# Fri3D_IRA_ESP32.net
KiCad netlist of a schematic drawn in Altium Designer
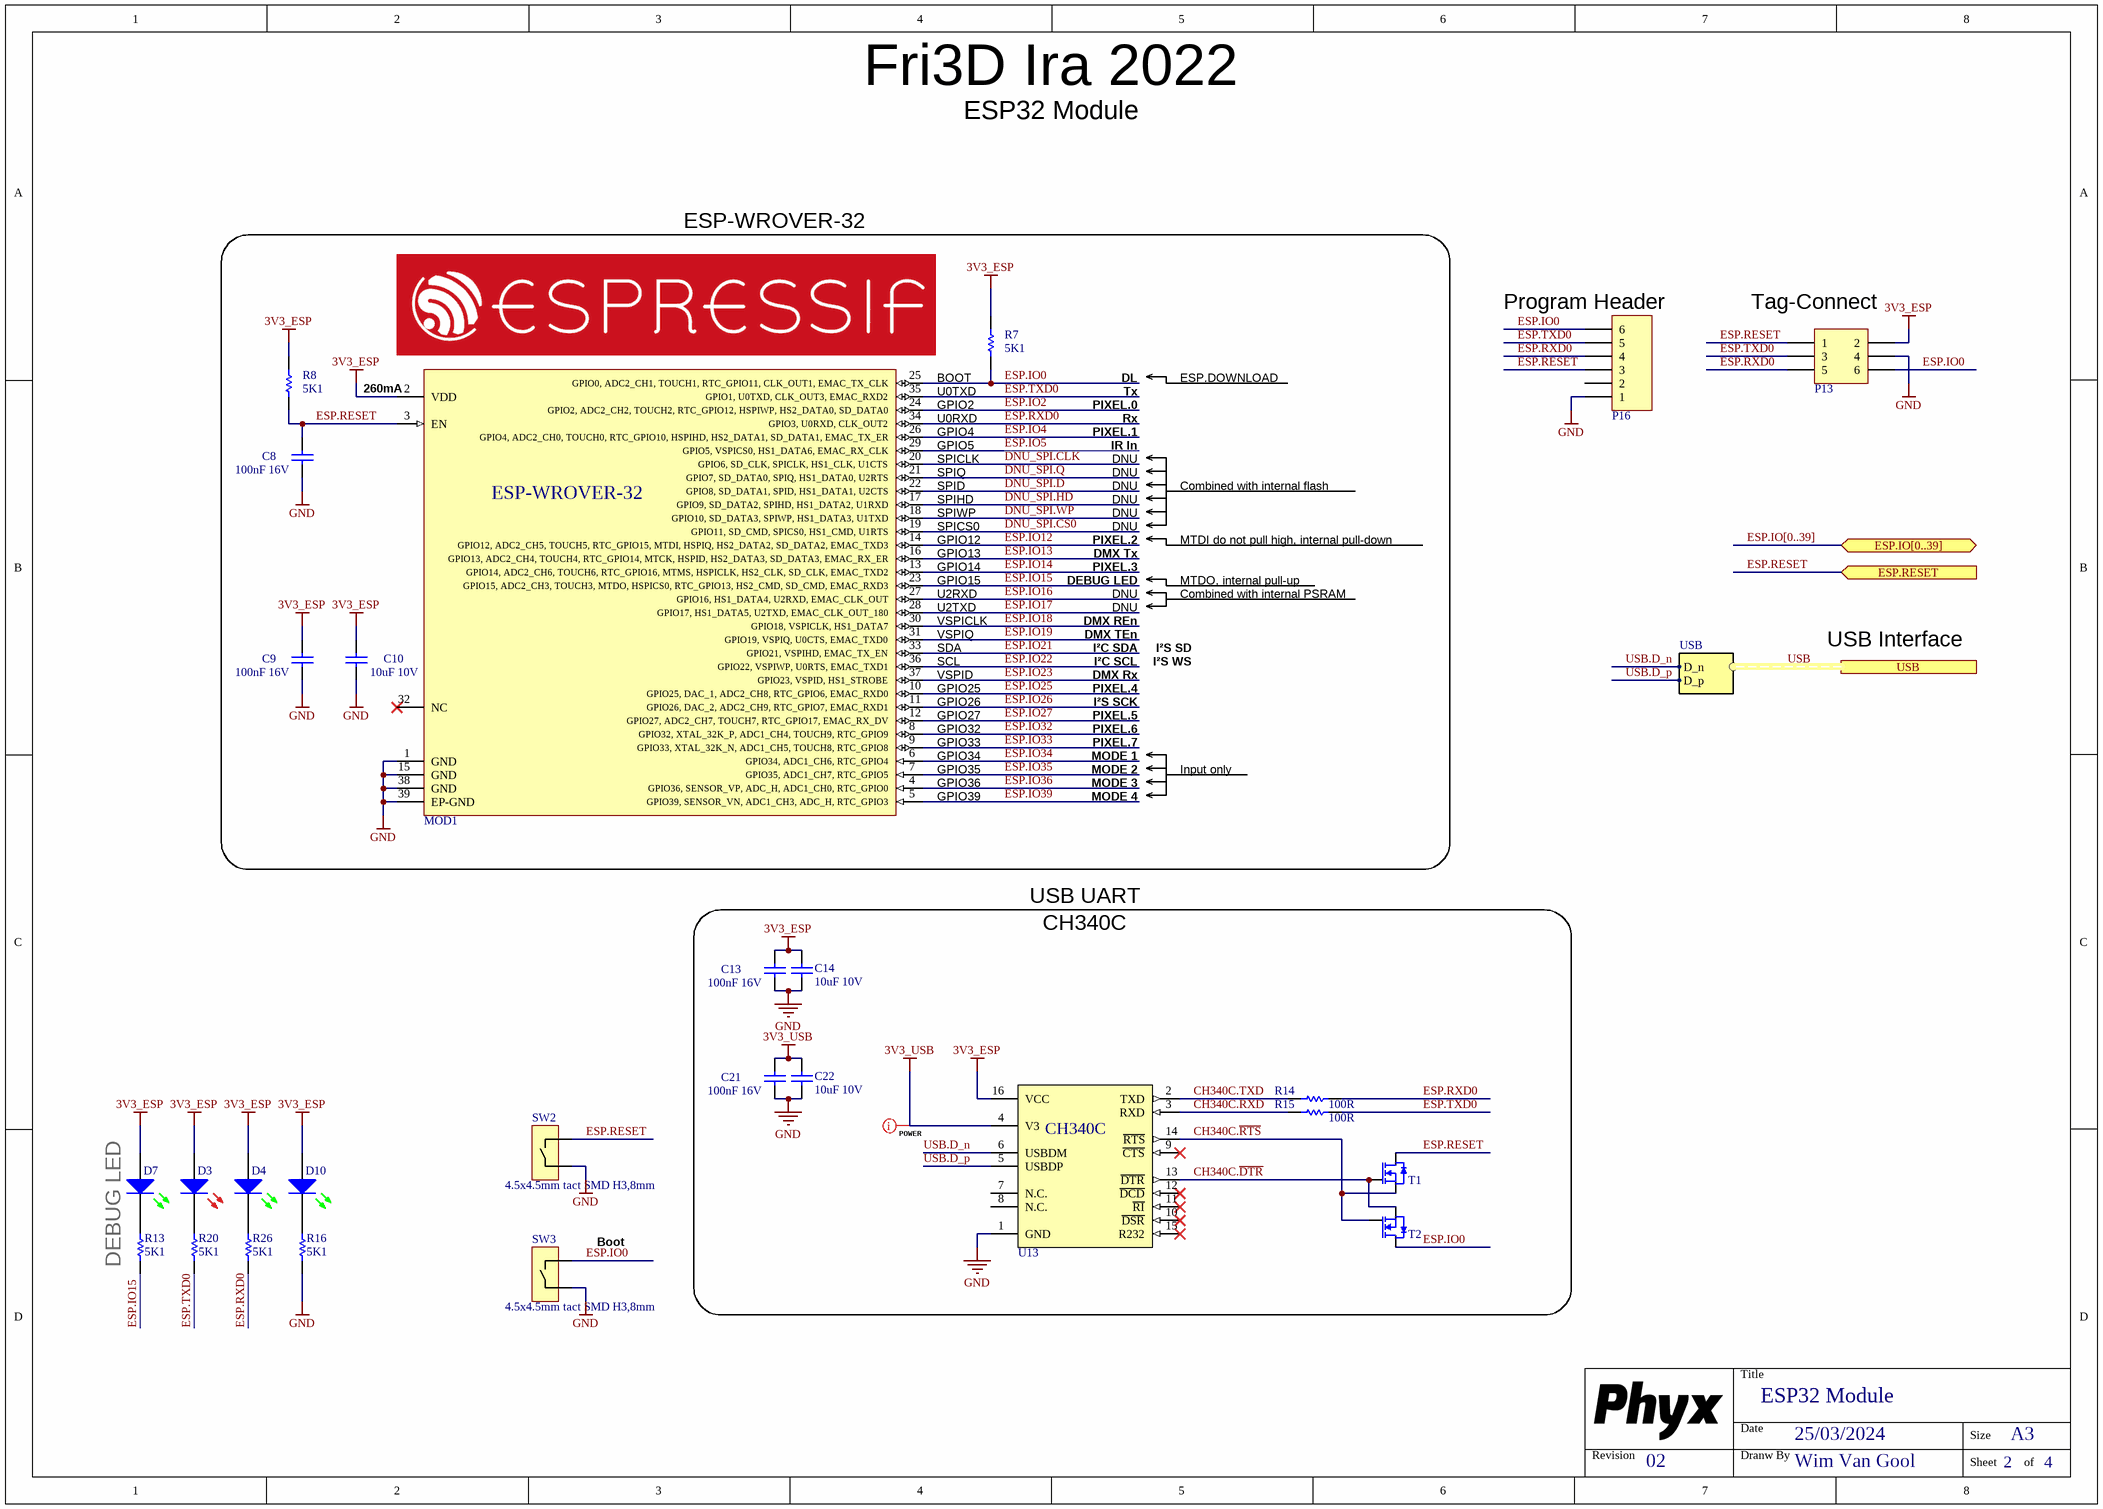
[diagram p0: Fri3D_IRA_ESP32.SchDoc]

(export (version "E")
  (design (tool "Eeschema 10.0.6"))
  (components
    (comp (ref "C8")
      (value "100nF 16V")
      (footprint "C0603_N")
      (description "Capacitor Ceramic")
      (libsource (lib "Phyx_Components") (part "CAP_CERAMIC"))
    )
    (comp (ref "C9")
      (value "100nF 16V")
      (footprint "C0603_N")
      (description "Capacitor Ceramic")
      (libsource (lib "Phyx_Components") (part "CAP_CERAMIC"))
    )
    (comp (ref "C10")
      (value "10uF 10V")
      (footprint "C0805_N")
      (description "Capacitor Ceramic")
      (libsource (lib "Phyx_Components") (part "CAP_CERAMIC"))
    )
    (comp (ref "C13")
      (value "100nF 16V")
      (footprint "C0603_N")
      (description "Capacitor Ceramic")
      (libsource (lib "Phyx_Components") (part "CAP_CERAMIC"))
    )
    (comp (ref "C14")
      (value "10uF 10V")
      (footprint "C0805_N")
      (description "Capacitor Ceramic")
      (libsource (lib "Phyx_Components") (part "CAP_CERAMIC"))
    )
    (comp (ref "C21")
      (value "100nF 16V")
      (footprint "C0603_N")
      (description "Capacitor Ceramic")
      (libsource (lib "Phyx_Components") (part "CAP_CERAMIC"))
    )
    (comp (ref "C22")
      (value "10uF 10V")
      (footprint "C0805_N")
      (description "Capacitor Ceramic")
      (libsource (lib "Phyx_Components") (part "CAP_CERAMIC"))
    )
    (comp (ref "D3")
      (value "Default 0805 Red LED")
      (footprint "LED_0805_RD")
      (description "=Description")
      (libsource (lib "Phyx_Components") (part "LED_RED"))
    )
    (comp (ref "D4")
      (value "Default 0805 Green LED")
      (footprint "LED_0805_GR")
      (description "=Description")
      (libsource (lib "Phyx_Components") (part "LED_GREEN"))
    )
    (comp (ref "D7")
      (value "Default 0805 Green LED")
      (footprint "LED_0805_GR")
      (description "=Description")
      (libsource (lib "Phyx_Components") (part "LED_GREEN"))
    )
    (comp (ref "D10")
      (value "Default 0805 Green LED")
      (footprint "LED_0805_GR")
      (description "=Description")
      (libsource (lib "Phyx_Components") (part "LED_GREEN"))
    )
    (comp (ref "MOD1")
      (value "ESP-32 based ESP-WROVER-32")
      (footprint "ESP-WROVER-32")
      (description "WiFi # MOD ESP-WROVER-32")
      (libsource (lib "Phyx_Components") (part "ESP-WROVER-32"))
    )
    (comp (ref "P13")
      (value "6 pin tagconnect TC2030")
      (footprint "TC2030")
      (libsource (lib "Phyx_Components") (part "Header 3X2"))
    )
    (comp (ref "P16")
      (value "Header 6")
      (footprint "HDR1X6")
      (libsource (lib "Phyx_Components") (part "Header 6"))
    )
    (comp (ref "R7")
      (value "5K1")
      (footprint "R0603_N")
      (libsource (lib "Phyx_Components") (part "RESISTOR"))
    )
    (comp (ref "R8")
      (value "5K1")
      (footprint "R0603_N")
      (libsource (lib "Phyx_Components") (part "RESISTOR"))
    )
    (comp (ref "R13")
      (value "5K1")
      (footprint "R0603_N")
      (libsource (lib "Phyx_Components") (part "RESISTOR"))
    )
    (comp (ref "R14")
      (value "100R")
      (footprint "R0603_N")
      (libsource (lib "Phyx_Components") (part "RESISTOR"))
    )
    (comp (ref "R15")
      (value "100R")
      (footprint "R0603_N")
      (libsource (lib "Phyx_Components") (part "RESISTOR"))
    )
    (comp (ref "R16")
      (value "5K1")
      (footprint "R0603_N")
      (libsource (lib "Phyx_Components") (part "RESISTOR"))
    )
    (comp (ref "R20")
      (value "5K1")
      (footprint "R0603_N")
      (description "RES # 5K1 0603")
      (libsource (lib "Phyx_Components") (part "RESISTOR"))
    )
    (comp (ref "R26")
      (value "5K1")
      (footprint "R0603_N")
      (description "RES # 5K1 0603")
      (libsource (lib "Phyx_Components") (part "RESISTOR"))
    )
    (comp (ref "SW2")
      (value "4.5x4.5mm tact SMD H3,8mm")
      (footprint "WE_430181038816")
      (libsource (lib "Phyx_Components") (part "SW_TACT"))
    )
    (comp (ref "SW3")
      (value "4.5x4.5mm tact SMD H3,8mm")
      (footprint "WE_430181038816")
      (libsource (lib "Phyx_Components") (part "SW_TACT"))
    )
    (comp (ref "T1")
      (value "0.2A N-Ch MOSFET Vgs 3.2")
      (footprint "SOT23-3")
      (libsource (lib "Phyx_Components") (part "N_MOSFET_GSD"))
    )
    (comp (ref "T2")
      (value "0.2A N-Ch MOSFET Vgs 3.2")
      (footprint "SOT23-3")
      (libsource (lib "Phyx_Components") (part "N_MOSFET_GSD"))
    )
    (comp (ref "U13")
      (value "USB to full UART with internal crystal")
      (footprint "SOIC_N_16")
      (description "=Description")
      (libsource (lib "Phyx_Components") (part "CH340C"))
    )
  )
  (nets
    (net (code "18") (name "/CH340C.RXD") (class "Default")
      (node (ref "R15") (pin "1") (pinfunction "1_1") (pintype "passive"))
      (node (ref "U13") (pin "3") (pinfunction "RXD_3") (pintype "input"))
    )
    (net (code "19") (name "/CH340C.TXD") (class "Default")
      (node (ref "R14") (pin "1") (pinfunction "1_1") (pintype "passive"))
      (node (ref "U13") (pin "2") (pinfunction "TXD_2") (pintype "output"))
    )
    (net (code "20") (name "/CH340C.~{DTR}") (class "Default")
      (node (ref "T1") (pin "1") (pinfunction "G_1") (pintype "passive"))
      (node (ref "T2") (pin "2") (pinfunction "S_2") (pintype "passive"))
      (node (ref "U13") (pin "13") (pinfunction "~{DTR}_13") (pintype "output"))
    )
    (net (code "21") (name "/CH340C.~{RTS}") (class "Default")
      (node (ref "T1") (pin "2") (pinfunction "S_2") (pintype "passive"))
      (node (ref "T2") (pin "1") (pinfunction "G_1") (pintype "passive"))
      (node (ref "U13") (pin "14") (pinfunction "~{RTS}_14") (pintype "output"))
    )
    (net (code "22") (name "/DNU_SPI.CLK") (class "Default")
      (node (ref "MOD1") (pin "20") (pinfunction "GPIO6,_SD_CLK,_SPICLK,_HS1_CLK,_U1CTS_20") (pintype "bidirectional"))
    )
    (net (code "23") (name "/DNU_SPI.CS0") (class "Default")
      (node (ref "MOD1") (pin "19") (pinfunction "GPIO11,_SD_CMD,_SPICS0,_HS1_CMD,_U1RTS_19") (pintype "bidirectional"))
    )
    (net (code "24") (name "/DNU_SPI.D") (class "Default")
      (node (ref "MOD1") (pin "22") (pinfunction "GPIO8,_SD_DATA1,_SPID,_HS1_DATA1,_U2CTS_22") (pintype "bidirectional"))
    )
    (net (code "25") (name "/DNU_SPI.HD") (class "Default")
      (node (ref "MOD1") (pin "17") (pinfunction "GPIO9,_SD_DATA2,_SPIHD,_HS1_DATA2,_U1RXD_17") (pintype "bidirectional"))
    )
    (net (code "26") (name "/DNU_SPI.Q") (class "Default")
      (node (ref "MOD1") (pin "21") (pinfunction "GPIO7,_SD_DATA0,_SPIQ,_HS1_DATA0,_U2RTS_21") (pintype "bidirectional"))
    )
    (net (code "27") (name "/DNU_SPI.WP") (class "Default")
      (node (ref "MOD1") (pin "18") (pinfunction "GPIO10,_SD_DATA3,_SPIWP,_HS1_DATA3,_U1TXD_18") (pintype "bidirectional"))
    )
    (net (code "28") (name "/ESP.IO0") (class "Default")
      (node (ref "MOD1") (pin "25") (pinfunction "GPIO0,_ADC2_CH1,_TOUCH1,_RTC_GPIO11,_CLK_OUT1,_EMAC_TX_CLK_25") (pintype "bidirectional"))
      (node (ref "P13") (pin "6") (pinfunction "6_6") (pintype "passive"))
      (node (ref "P16") (pin "6") (pinfunction "6_6") (pintype "passive"))
      (node (ref "R7") (pin "2") (pinfunction "2_2") (pintype "passive"))
      (node (ref "SW3") (pin "1") (pinfunction "1_1") (pintype "passive"))
      (node (ref "T2") (pin "3") (pinfunction "D_3") (pintype "passive"))
    )
    (net (code "29") (name "/ESP.IO2") (class "Default")
      (node (ref "MOD1") (pin "24") (pinfunction "GPIO2,_ADC2_CH2,_TOUCH2,_RTC_GPIO12,_HSPIWP,_HS2_DATA0,_SD_DATA0_24") (pintype "bidirectional"))
    )
    (net (code "30") (name "/ESP.IO4") (class "Default")
      (node (ref "MOD1") (pin "26") (pinfunction "GPIO4,_ADC2_CH0,_TOUCH0,_RTC_GPIO10,_HSPIHD,_HS2_DATA1,_SD_DATA1,_EMAC_TX_ER_26") (pintype "bidirectional"))
    )
    (net (code "31") (name "/ESP.IO5") (class "Default")
      (node (ref "MOD1") (pin "29") (pinfunction "GPIO5,_VSPICS0,_HS1_DATA6,_EMAC_RX_CLK_29") (pintype "bidirectional"))
    )
    (net (code "32") (name "/ESP.IO12") (class "Default")
      (node (ref "MOD1") (pin "14") (pinfunction "GPIO12,_ADC2_CH5,_TOUCH5,_RTC_GPIO15,_MTDI,_HSPIQ,_HS2_DATA2,_SD_DATA2,_EMAC_TXD3_14") (pintype "bidirectional"))
    )
    (net (code "33") (name "/ESP.IO13") (class "Default")
      (node (ref "MOD1") (pin "16") (pinfunction "GPIO13,_ADC2_CH4,_TOUCH4,_RTC_GPIO14,_MTCK,_HSPID,_HS2_DATA3,_SD_DATA3,_EMAC_RX_ER_16") (pintype "bidirectional"))
    )
    (net (code "34") (name "/ESP.IO14") (class "Default")
      (node (ref "MOD1") (pin "13") (pinfunction "GPIO14,_ADC2_CH6,_TOUCH6,_RTC_GPIO16,_MTMS,_HSPICLK,_HS2_CLK,_SD_CLK,_EMAC_TXD2_13") (pintype "bidirectional"))
    )
    (net (code "35") (name "/ESP.IO15") (class "Default")
      (node (ref "MOD1") (pin "23") (pinfunction "GPIO15,_ADC2_CH3,_TOUCH3,_MTDO,_HSPICS0,_RTC_GPIO13,_HS2_CMD,_SD_CMD,_EMAC_RXD3_23") (pintype "bidirectional"))
      (node (ref "R13") (pin "2") (pinfunction "2_2") (pintype "passive"))
    )
    (net (code "36") (name "/ESP.IO16") (class "Default")
      (node (ref "MOD1") (pin "27") (pinfunction "GPIO16,_HS1_DATA4,_U2RXD,_EMAC_CLK_OUT_27") (pintype "bidirectional"))
    )
    (net (code "37") (name "/ESP.IO17") (class "Default")
      (node (ref "MOD1") (pin "28") (pinfunction "GPIO17,_HS1_DATA5,_U2TXD,_EMAC_CLK_OUT_180_28") (pintype "bidirectional"))
    )
    (net (code "38") (name "/ESP.IO18") (class "Default")
      (node (ref "MOD1") (pin "30") (pinfunction "GPIO18,_VSPICLK,_HS1_DATA7_30") (pintype "bidirectional"))
    )
    (net (code "39") (name "/ESP.IO19") (class "Default")
      (node (ref "MOD1") (pin "31") (pinfunction "GPIO19,_VSPIQ,_U0CTS,_EMAC_TXD0_31") (pintype "bidirectional"))
    )
    (net (code "40") (name "/ESP.IO21") (class "Default")
      (node (ref "MOD1") (pin "33") (pinfunction "GPIO21,_VSPIHD,_EMAC_TX_EN_33") (pintype "bidirectional"))
    )
    (net (code "41") (name "/ESP.IO22") (class "Default")
      (node (ref "MOD1") (pin "36") (pinfunction "GPIO22,_VSPIWP,_U0RTS,_EMAC_TXD1_36") (pintype "bidirectional"))
    )
    (net (code "42") (name "/ESP.IO23") (class "Default")
      (node (ref "MOD1") (pin "37") (pinfunction "GPIO23,_VSPID,_HS1_STROBE_37") (pintype "bidirectional"))
    )
    (net (code "43") (name "/ESP.IO25") (class "Default")
      (node (ref "MOD1") (pin "10") (pinfunction "GPIO25,_DAC_1,_ADC2_CH8,_RTC_GPIO6,_EMAC_RXD0_10") (pintype "bidirectional"))
    )
    (net (code "44") (name "/ESP.IO26") (class "Default")
      (node (ref "MOD1") (pin "11") (pinfunction "GPIO26,_DAC_2,_ADC2_CH9,_RTC_GPIO7,_EMAC_RXD1_11") (pintype "bidirectional"))
    )
    (net (code "45") (name "/ESP.IO27") (class "Default")
      (node (ref "MOD1") (pin "12") (pinfunction "GPIO27,_ADC2_CH7,_TOUCH7,_RTC_GPIO17,_EMAC_RX_DV_12") (pintype "bidirectional"))
    )
    (net (code "46") (name "/ESP.IO32") (class "Default")
      (node (ref "MOD1") (pin "8") (pinfunction "GPIO32,_XTAL_32K_P,_ADC1_CH4,_TOUCH9,_RTC_GPIO9_8") (pintype "bidirectional"))
    )
    (net (code "47") (name "/ESP.IO33") (class "Default")
      (node (ref "MOD1") (pin "9") (pinfunction "GPIO33,_XTAL_32K_N,_ADC1_CH5,_TOUCH8,_RTC_GPIO8_9") (pintype "bidirectional"))
    )
    (net (code "48") (name "/ESP.IO34") (class "Default")
      (node (ref "MOD1") (pin "6") (pinfunction "GPIO34,_ADC1_CH6,_RTC_GPIO4_6") (pintype "input"))
    )
    (net (code "49") (name "/ESP.IO35") (class "Default")
      (node (ref "MOD1") (pin "7") (pinfunction "GPIO35,_ADC1_CH7,_RTC_GPIO5_7") (pintype "input"))
    )
    (net (code "50") (name "/ESP.IO36") (class "Default")
      (node (ref "MOD1") (pin "4") (pinfunction "GPIO36,_SENSOR_VP,_ADC_H,_ADC1_CH0,_RTC_GPIO0_4") (pintype "input"))
    )
    (net (code "51") (name "/ESP.IO39") (class "Default")
      (node (ref "MOD1") (pin "5") (pinfunction "GPIO39,_SENSOR_VN,_ADC1_CH3,_ADC_H,_RTC_GPIO3_5") (pintype "input"))
    )
    (net (code "53") (name "/ESP.RESET") (class "Default")
      (node (ref "C8") (pin "1") (pinfunction "1_1") (pintype "passive"))
      (node (ref "MOD1") (pin "3") (pinfunction "EN_3") (pintype "input"))
      (node (ref "P13") (pin "1") (pinfunction "1_1") (pintype "passive"))
      (node (ref "P16") (pin "3") (pinfunction "3_3") (pintype "passive"))
      (node (ref "R8") (pin "2") (pinfunction "2_2") (pintype "passive"))
      (node (ref "SW2") (pin "1") (pinfunction "1_1") (pintype "passive"))
      (node (ref "T1") (pin "3") (pinfunction "D_3") (pintype "passive"))
    )
    (net (code "54") (name "/ESP.RXD0") (class "Default")
      (node (ref "MOD1") (pin "34") (pinfunction "GPIO3,_U0RXD,_CLK_OUT2_34") (pintype "bidirectional"))
      (node (ref "P13") (pin "5") (pinfunction "5_5") (pintype "passive"))
      (node (ref "P16") (pin "4") (pinfunction "4_4") (pintype "passive"))
      (node (ref "R14") (pin "2") (pinfunction "2_2") (pintype "passive"))
      (node (ref "R26") (pin "2") (pinfunction "2_2") (pintype "passive"))
    )
    (net (code "55") (name "/ESP.TXD0") (class "Default")
      (node (ref "MOD1") (pin "35") (pinfunction "GPIO1,_U0TXD,_CLK_OUT3,_EMAC_RXD2_35") (pintype "bidirectional"))
      (node (ref "P13") (pin "3") (pinfunction "3_3") (pintype "passive"))
      (node (ref "P16") (pin "5") (pinfunction "5_5") (pintype "passive"))
      (node (ref "R15") (pin "2") (pinfunction "2_2") (pintype "passive"))
      (node (ref "R20") (pin "2") (pinfunction "2_2") (pintype "passive"))
    )
    (net (code "56") (name "/USB.D_n") (class "Default")
      (node (ref "U13") (pin "6") (pinfunction "USBDM_6") (pintype "passive"))
    )
    (net (code "57") (name "/USB.D_p") (class "Default")
      (node (ref "U13") (pin "5") (pinfunction "USBDP_5") (pintype "passive"))
    )
    (net (code "59") (name "3V3_ESP") (class "Default")
      (node (ref "C10") (pin "1") (pinfunction "1_1") (pintype "passive"))
      (node (ref "C13") (pin "1") (pinfunction "1_1") (pintype "passive"))
      (node (ref "C14") (pin "2") (pinfunction "2_2") (pintype "passive"))
      (node (ref "C9") (pin "1") (pinfunction "1_1") (pintype "passive"))
      (node (ref "D10") (pin "1") (pinfunction "A_1") (pintype "passive"))
      (node (ref "D3") (pin "1") (pinfunction "A_1") (pintype "passive"))
      (node (ref "D4") (pin "1") (pinfunction "A_1") (pintype "passive"))
      (node (ref "D7") (pin "1") (pinfunction "A_1") (pintype "passive"))
      (node (ref "MOD1") (pin "2") (pinfunction "VDD_2") (pintype "power_in"))
      (node (ref "P13") (pin "2") (pinfunction "2_2") (pintype "passive"))
      (node (ref "R7") (pin "1") (pinfunction "1_1") (pintype "passive"))
      (node (ref "R8") (pin "1") (pinfunction "1_1") (pintype "passive"))
      (node (ref "U13") (pin "16") (pinfunction "VCC_16") (pintype "power_in"))
    )
    (net (code "60") (name "3V3_USB") (class "Default")
      (node (ref "C21") (pin "1") (pinfunction "1_1") (pintype "passive"))
      (node (ref "C22") (pin "2") (pinfunction "2_2") (pintype "passive"))
      (node (ref "U13") (pin "4") (pinfunction "V3_4") (pintype "power_in"))
    )
    (net (code "61") (name "GND") (class "Default")
      (node (ref "C10") (pin "2") (pinfunction "2_2") (pintype "passive"))
      (node (ref "C13") (pin "2") (pinfunction "2_2") (pintype "passive"))
      (node (ref "C14") (pin "1") (pinfunction "1_1") (pintype "passive"))
      (node (ref "C21") (pin "2") (pinfunction "2_2") (pintype "passive"))
      (node (ref "C22") (pin "1") (pinfunction "1_1") (pintype "passive"))
      (node (ref "C8") (pin "2") (pinfunction "2_2") (pintype "passive"))
      (node (ref "C9") (pin "2") (pinfunction "2_2") (pintype "passive"))
      (node (ref "MOD1") (pin "1") (pinfunction "GND_1") (pintype "power_in"))
      (node (ref "MOD1") (pin "15") (pinfunction "GND_15") (pintype "power_in"))
      (node (ref "MOD1") (pin "38") (pinfunction "GND_38") (pintype "power_in"))
      (node (ref "MOD1") (pin "39") (pinfunction "EP-GND_39") (pintype "power_in"))
      (node (ref "P13") (pin "4") (pinfunction "4_4") (pintype "passive"))
      (node (ref "P16") (pin "1") (pinfunction "1_1") (pintype "passive"))
      (node (ref "R16") (pin "2") (pinfunction "2_2") (pintype "passive"))
      (node (ref "SW2") (pin "2") (pinfunction "2_2") (pintype "passive"))
      (node (ref "SW3") (pin "2") (pinfunction "2_2") (pintype "passive"))
      (node (ref "U13") (pin "1") (pinfunction "GND_1") (pintype "power_in"))
    )
    (net (code "62") (name "Net-(D3-K)") (class "Default")
      (node (ref "D3") (pin "2") (pinfunction "K_2") (pintype "passive"))
      (node (ref "R20") (pin "1") (pinfunction "1_1") (pintype "passive"))
    )
    (net (code "63") (name "Net-(D4-K)") (class "Default")
      (node (ref "D4") (pin "2") (pinfunction "K_2") (pintype "passive"))
      (node (ref "R26") (pin "1") (pinfunction "1_1") (pintype "passive"))
    )
    (net (code "64") (name "Net-(D7-K)") (class "Default")
      (node (ref "D7") (pin "2") (pinfunction "K_2") (pintype "passive"))
      (node (ref "R13") (pin "1") (pinfunction "1_1") (pintype "passive"))
    )
    (net (code "65") (name "Net-(D10-K)") (class "Default")
      (node (ref "D10") (pin "2") (pinfunction "K_2") (pintype "passive"))
      (node (ref "R16") (pin "1") (pinfunction "1_1") (pintype "passive"))
    )
    (net (code "66") (name "unconnected-(MOD1-NC-Pad32)") (class "Default")
      (node (ref "MOD1") (pin "32") (pinfunction "NC_32") (pintype "passive+no_connect"))
    )
    (net (code "67") (name "unconnected-(P16-Pad2)") (class "Default")
      (node (ref "P16") (pin "2") (pinfunction "2_2") (pintype "passive"))
    )
    (net (code "68") (name "unconnected-(U13-N.C.-Pad7)") (class "Default")
      (node (ref "U13") (pin "7") (pinfunction "N.C._7") (pintype "passive"))
    )
    (net (code "69") (name "unconnected-(U13-N.C.-Pad8)") (class "Default")
      (node (ref "U13") (pin "8") (pinfunction "N.C._8") (pintype "passive"))
    )
    (net (code "70") (name "unconnected-(U13-R232-Pad15)") (class "Default")
      (node (ref "U13") (pin "15") (pinfunction "R232_15") (pintype "input+no_connect"))
    )
    (net (code "71") (name "unconnected-(U13-~{CTS}-Pad9)") (class "Default")
      (node (ref "U13") (pin "9") (pinfunction "~{CTS}_9") (pintype "input+no_connect"))
    )
    (net (code "72") (name "unconnected-(U13-~{DCD}-Pad12)") (class "Default")
      (node (ref "U13") (pin "12") (pinfunction "~{DCD}_12") (pintype "input+no_connect"))
    )
    (net (code "73") (name "unconnected-(U13-~{DSR}-Pad10)") (class "Default")
      (node (ref "U13") (pin "10") (pinfunction "~{DSR}_10") (pintype "input+no_connect"))
    )
    (net (code "74") (name "unconnected-(U13-~{RI}-Pad11)") (class "Default")
      (node (ref "U13") (pin "11") (pinfunction "~{RI}_11") (pintype "input+no_connect"))
    )
  )
)
